# main.net
KiCad netlist of a schematic drawn in EAGLE
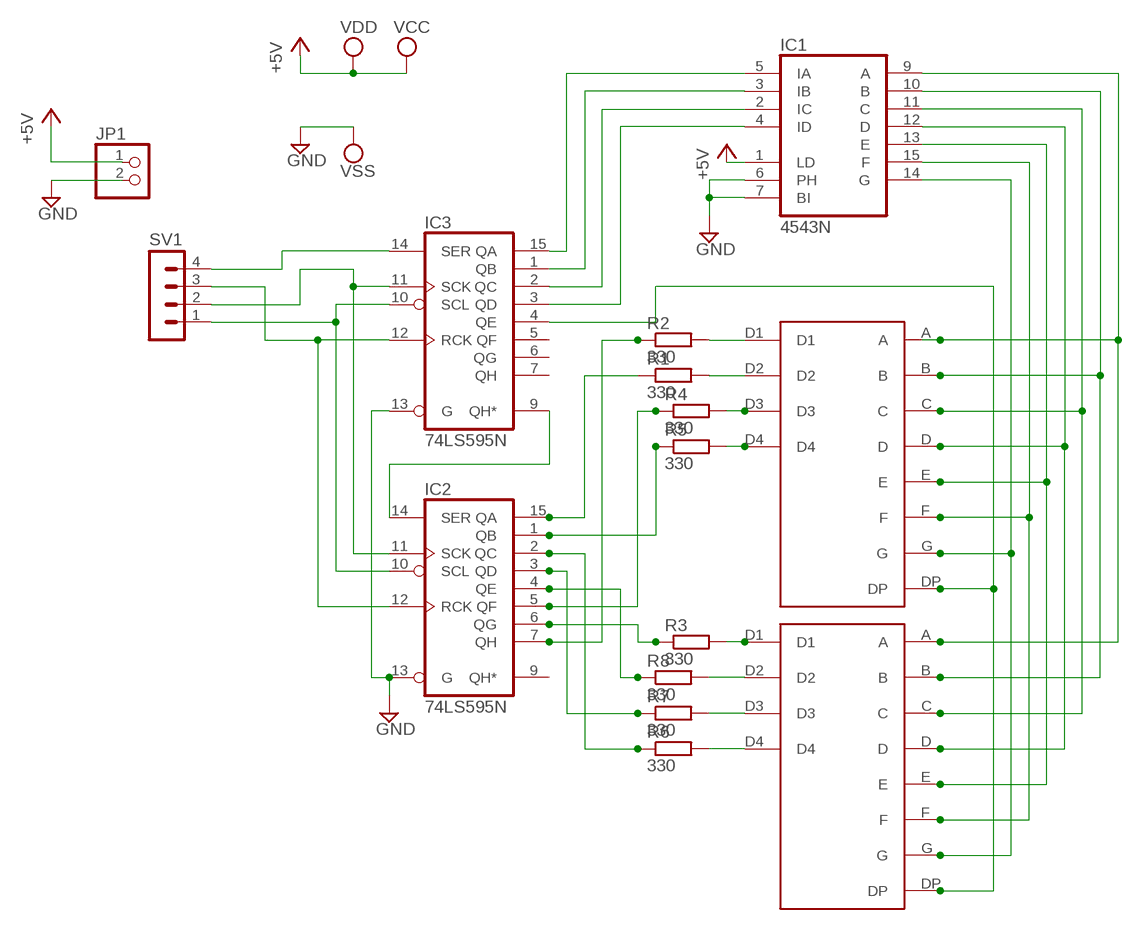
[diagram p0: schematic, sheet 1]

(export (version "E")
  (design (tool "Eeschema 10.0.6"))
  (components
    (comp (ref "IC1")
      (value "4543N")
      (footprint "eagle-import:DIL16")
      (libsource (lib "eagle-import") (part "4543N"))
    )
    (comp (ref "IC2")
      (value "74LS595N")
      (footprint "eagle-import:DIL16")
      (libsource (lib "eagle-import") (part "74595NLS"))
    )
    (comp (ref "IC3")
      (value "74LS595N")
      (footprint "eagle-import:DIL16")
      (libsource (lib "eagle-import") (part "74595NLS"))
    )
    (comp (ref "JP1")
      (value "PINHD-1X2")
      (footprint "eagle-import:1X02")
      (libsource (lib "eagle-import") (part "PINHD-1X2"))
    )
    (comp (ref "R1")
      (value "330")
      (footprint "eagle-import:P0817_22")
      (libsource (lib "eagle-import") (part "R-EU_0817/22"))
    )
    (comp (ref "R2")
      (value "330")
      (footprint "eagle-import:R0805")
      (libsource (lib "eagle-import") (part "R-EU_R0805"))
    )
    (comp (ref "R3")
      (value "330")
      (footprint "eagle-import:R0805")
      (libsource (lib "eagle-import") (part "R-EU_R0805"))
    )
    (comp (ref "R4")
      (value "330")
      (footprint "eagle-import:R0805")
      (libsource (lib "eagle-import") (part "R-EU_R0805"))
    )
    (comp (ref "R5")
      (value "330")
      (footprint "eagle-import:R0805")
      (libsource (lib "eagle-import") (part "R-EU_R0805"))
    )
    (comp (ref "R6")
      (value "330")
      (footprint "eagle-import:R0805")
      (libsource (lib "eagle-import") (part "R-EU_R0805"))
    )
    (comp (ref "R7")
      (value "330")
      (footprint "eagle-import:R0805")
      (libsource (lib "eagle-import") (part "R-EU_R0805"))
    )
    (comp (ref "R8")
      (value "330")
      (footprint "eagle-import:R0805")
      (libsource (lib "eagle-import") (part "R-EU_R0805"))
    )
    (comp (ref "SV1")
      (value "MA04-1")
      (footprint "eagle-import:MA04-1")
      (libsource (lib "eagle-import") (part "MA04-1"))
    )
    (comp (ref "U$1")
      (value "4-DIGIT_7-SEGMENT-DISPLAYTHROUGH-HOLE")
      (footprint "eagle-import:4-DIGIT_7-SEGMENT-DISPLAY")
      (libsource (lib "eagle-import") (part "4-DIGIT_7-SEGMENT-DISPLAYTHROUGH-HOLE"))
    )
    (comp (ref "U$2")
      (value "4-DIGIT_7-SEGMENT-DISPLAYTHROUGH-HOLE")
      (footprint "eagle-import:4-DIGIT_7-SEGMENT-DISPLAY")
      (libsource (lib "eagle-import") (part "4-DIGIT_7-SEGMENT-DISPLAYTHROUGH-HOLE"))
    )
  )
  (nets
    (net (code "1") (name "+5V") (class "Default")
      (node (ref "IC1") (pin "1") (pinfunction "LD_1") (pintype "input"))
      (node (ref "JP1") (pin "1") (pinfunction "1_1") (pintype "passive"))
    )
    (net (code "2") (name "GND") (class "Default")
      (node (ref "IC1") (pin "6") (pinfunction "PH_6") (pintype "input"))
      (node (ref "IC1") (pin "7") (pinfunction "BI_7") (pintype "input"))
      (node (ref "IC2") (pin "13") (pinfunction "G_13") (pintype "input"))
      (node (ref "IC3") (pin "13") (pinfunction "G_13") (pintype "input"))
      (node (ref "JP1") (pin "2") (pinfunction "2_2") (pintype "passive"))
    )
    (net (code "3") (name "Net-(IC1A-A)") (class "Default")
      (node (ref "IC1") (pin "9") (pinfunction "A_9") (pintype "output"))
      (node (ref "U$1") (pin "A") (pinfunction "A_A") (pintype "bidirectional"))
      (node (ref "U$2") (pin "A") (pinfunction "A_A") (pintype "bidirectional"))
    )
    (net (code "4") (name "Net-(IC1A-B)") (class "Default")
      (node (ref "IC1") (pin "10") (pinfunction "B_10") (pintype "output"))
      (node (ref "U$1") (pin "B") (pinfunction "B_B") (pintype "bidirectional"))
      (node (ref "U$2") (pin "B") (pinfunction "B_B") (pintype "bidirectional"))
    )
    (net (code "5") (name "Net-(IC1A-C)") (class "Default")
      (node (ref "IC1") (pin "11") (pinfunction "C_11") (pintype "output"))
      (node (ref "U$1") (pin "C") (pinfunction "C_C") (pintype "bidirectional"))
      (node (ref "U$2") (pin "C") (pinfunction "C_C") (pintype "bidirectional"))
    )
    (net (code "6") (name "Net-(IC1A-D)") (class "Default")
      (node (ref "IC1") (pin "12") (pinfunction "D_12") (pintype "output"))
      (node (ref "U$1") (pin "D") (pinfunction "D_D") (pintype "bidirectional"))
      (node (ref "U$2") (pin "D") (pinfunction "D_D") (pintype "bidirectional"))
    )
    (net (code "7") (name "Net-(IC1A-E)") (class "Default")
      (node (ref "IC1") (pin "13") (pinfunction "E_13") (pintype "output"))
      (node (ref "U$1") (pin "E") (pinfunction "E_E") (pintype "bidirectional"))
      (node (ref "U$2") (pin "E") (pinfunction "E_E") (pintype "bidirectional"))
    )
    (net (code "8") (name "Net-(IC1A-F)") (class "Default")
      (node (ref "IC1") (pin "15") (pinfunction "F_15") (pintype "output"))
      (node (ref "U$1") (pin "F") (pinfunction "F_F") (pintype "bidirectional"))
      (node (ref "U$2") (pin "F") (pinfunction "F_F") (pintype "bidirectional"))
    )
    (net (code "9") (name "Net-(IC1A-G)") (class "Default")
      (node (ref "IC1") (pin "14") (pinfunction "G_14") (pintype "output"))
      (node (ref "U$1") (pin "G") (pinfunction "G_G") (pintype "bidirectional"))
      (node (ref "U$2") (pin "G") (pinfunction "G_G") (pintype "bidirectional"))
    )
    (net (code "10") (name "Net-(IC1A-IA)") (class "Default")
      (node (ref "IC1") (pin "5") (pinfunction "IA_5") (pintype "input"))
      (node (ref "IC3") (pin "15") (pinfunction "QA_15") (pintype "tri_state"))
    )
    (net (code "11") (name "Net-(IC1A-IB)") (class "Default")
      (node (ref "IC1") (pin "3") (pinfunction "IB_3") (pintype "input"))
      (node (ref "IC3") (pin "1") (pinfunction "QB_1") (pintype "tri_state"))
    )
    (net (code "12") (name "Net-(IC1A-IC)") (class "Default")
      (node (ref "IC1") (pin "2") (pinfunction "IC_2") (pintype "input"))
      (node (ref "IC3") (pin "2") (pinfunction "QC_2") (pintype "tri_state"))
    )
    (net (code "13") (name "Net-(IC1A-ID)") (class "Default")
      (node (ref "IC1") (pin "4") (pinfunction "ID_4") (pintype "input"))
      (node (ref "IC3") (pin "3") (pinfunction "QD_3") (pintype "tri_state"))
    )
    (net (code "14") (name "Net-(IC2A-QA)") (class "Default")
      (node (ref "IC2") (pin "15") (pinfunction "QA_15") (pintype "tri_state"))
      (node (ref "R1") (pin "1") (pinfunction "1_1") (pintype "passive"))
    )
    (net (code "15") (name "Net-(IC2A-QB)") (class "Default")
      (node (ref "IC2") (pin "1") (pinfunction "QB_1") (pintype "tri_state"))
      (node (ref "R5") (pin "1") (pinfunction "1_1") (pintype "passive"))
    )
    (net (code "16") (name "Net-(IC2A-QC)") (class "Default")
      (node (ref "IC2") (pin "2") (pinfunction "QC_2") (pintype "tri_state"))
      (node (ref "R6") (pin "1") (pinfunction "1_1") (pintype "passive"))
    )
    (net (code "17") (name "Net-(IC2A-QD)") (class "Default")
      (node (ref "IC2") (pin "3") (pinfunction "QD_3") (pintype "tri_state"))
      (node (ref "R7") (pin "1") (pinfunction "1_1") (pintype "passive"))
    )
    (net (code "18") (name "Net-(IC2A-QE)") (class "Default")
      (node (ref "IC2") (pin "4") (pinfunction "QE_4") (pintype "tri_state"))
      (node (ref "R8") (pin "1") (pinfunction "1_1") (pintype "passive"))
    )
    (net (code "19") (name "Net-(IC2A-QF)") (class "Default")
      (node (ref "IC2") (pin "5") (pinfunction "QF_5") (pintype "tri_state"))
      (node (ref "R4") (pin "1") (pinfunction "1_1") (pintype "passive"))
    )
    (net (code "20") (name "Net-(IC2A-QG)") (class "Default")
      (node (ref "IC2") (pin "6") (pinfunction "QG_6") (pintype "tri_state"))
      (node (ref "R3") (pin "1") (pinfunction "1_1") (pintype "passive"))
    )
    (net (code "21") (name "Net-(IC2A-QH)") (class "Default")
      (node (ref "IC2") (pin "7") (pinfunction "QH_7") (pintype "tri_state"))
      (node (ref "R2") (pin "1") (pinfunction "1_1") (pintype "passive"))
    )
    (net (code "22") (name "Net-(IC2A-RCK)") (class "Default")
      (node (ref "IC2") (pin "12") (pinfunction "RCK_12") (pintype "input"))
      (node (ref "IC3") (pin "12") (pinfunction "RCK_12") (pintype "input"))
      (node (ref "SV1") (pin "3") (pinfunction "3_3") (pintype "passive"))
    )
    (net (code "23") (name "Net-(IC2A-SCK)") (class "Default")
      (node (ref "IC2") (pin "11") (pinfunction "SCK_11") (pintype "input"))
      (node (ref "IC3") (pin "11") (pinfunction "SCK_11") (pintype "input"))
      (node (ref "SV1") (pin "2") (pinfunction "2_2") (pintype "passive"))
    )
    (net (code "24") (name "Net-(IC2A-SCL)") (class "Default")
      (node (ref "IC2") (pin "10") (pinfunction "SCL_10") (pintype "input"))
      (node (ref "IC3") (pin "10") (pinfunction "SCL_10") (pintype "input"))
      (node (ref "SV1") (pin "1") (pinfunction "1_1") (pintype "passive"))
    )
    (net (code "25") (name "Net-(IC2A-SER)") (class "Default")
      (node (ref "IC2") (pin "14") (pinfunction "SER_14") (pintype "input"))
      (node (ref "IC3") (pin "9") (pinfunction "QH*_9") (pintype "tri_state"))
    )
    (net (code "26") (name "Net-(IC3A-QE)") (class "Default")
      (node (ref "IC3") (pin "4") (pinfunction "QE_4") (pintype "tri_state"))
      (node (ref "U$1") (pin "DP") (pinfunction "DP_DP") (pintype "bidirectional"))
      (node (ref "U$2") (pin "DP") (pinfunction "DP_DP") (pintype "bidirectional"))
    )
    (net (code "27") (name "Net-(IC3A-SER)") (class "Default")
      (node (ref "IC3") (pin "14") (pinfunction "SER_14") (pintype "input"))
      (node (ref "SV1") (pin "4") (pinfunction "4_4") (pintype "passive"))
    )
    (net (code "28") (name "Net-(R1-Pad2)") (class "Default")
      (node (ref "R1") (pin "2") (pinfunction "2_2") (pintype "passive"))
      (node (ref "U$1") (pin "D2") (pinfunction "D2_D2") (pintype "bidirectional"))
    )
    (net (code "29") (name "Net-(R2-Pad2)") (class "Default")
      (node (ref "R2") (pin "2") (pinfunction "2_2") (pintype "passive"))
      (node (ref "U$1") (pin "D1") (pinfunction "D1_D1") (pintype "bidirectional"))
    )
    (net (code "30") (name "Net-(R3-Pad2)") (class "Default")
      (node (ref "R3") (pin "2") (pinfunction "2_2") (pintype "passive"))
      (node (ref "U$2") (pin "D1") (pinfunction "D1_D1") (pintype "bidirectional"))
    )
    (net (code "31") (name "Net-(R4-Pad2)") (class "Default")
      (node (ref "R4") (pin "2") (pinfunction "2_2") (pintype "passive"))
      (node (ref "U$1") (pin "D3") (pinfunction "D3_D3") (pintype "bidirectional"))
    )
    (net (code "32") (name "Net-(R5-Pad2)") (class "Default")
      (node (ref "R5") (pin "2") (pinfunction "2_2") (pintype "passive"))
      (node (ref "U$1") (pin "D4") (pinfunction "D4_D4") (pintype "bidirectional"))
    )
    (net (code "33") (name "Net-(R6-Pad2)") (class "Default")
      (node (ref "R6") (pin "2") (pinfunction "2_2") (pintype "passive"))
      (node (ref "U$2") (pin "D4") (pinfunction "D4_D4") (pintype "bidirectional"))
    )
    (net (code "34") (name "Net-(R7-Pad2)") (class "Default")
      (node (ref "R7") (pin "2") (pinfunction "2_2") (pintype "passive"))
      (node (ref "U$2") (pin "D3") (pinfunction "D3_D3") (pintype "bidirectional"))
    )
    (net (code "35") (name "Net-(R8-Pad2)") (class "Default")
      (node (ref "R8") (pin "2") (pinfunction "2_2") (pintype "passive"))
      (node (ref "U$2") (pin "D2") (pinfunction "D2_D2") (pintype "bidirectional"))
    )
    (net (code "36") (name "unconnected-(IC2A-QH*-Pad9)") (class "Default")
      (node (ref "IC2") (pin "9") (pinfunction "QH*_9") (pintype "tri_state"))
    )
    (net (code "37") (name "unconnected-(IC3A-QF-Pad5)") (class "Default")
      (node (ref "IC3") (pin "5") (pinfunction "QF_5") (pintype "tri_state"))
    )
    (net (code "38") (name "unconnected-(IC3A-QG-Pad6)") (class "Default")
      (node (ref "IC3") (pin "6") (pinfunction "QG_6") (pintype "tri_state"))
    )
    (net (code "39") (name "unconnected-(IC3A-QH-Pad7)") (class "Default")
      (node (ref "IC3") (pin "7") (pinfunction "QH_7") (pintype "tri_state"))
    )
  )
)
